# io.net
KiCad netlist of a schematic drawn in Altium Designer
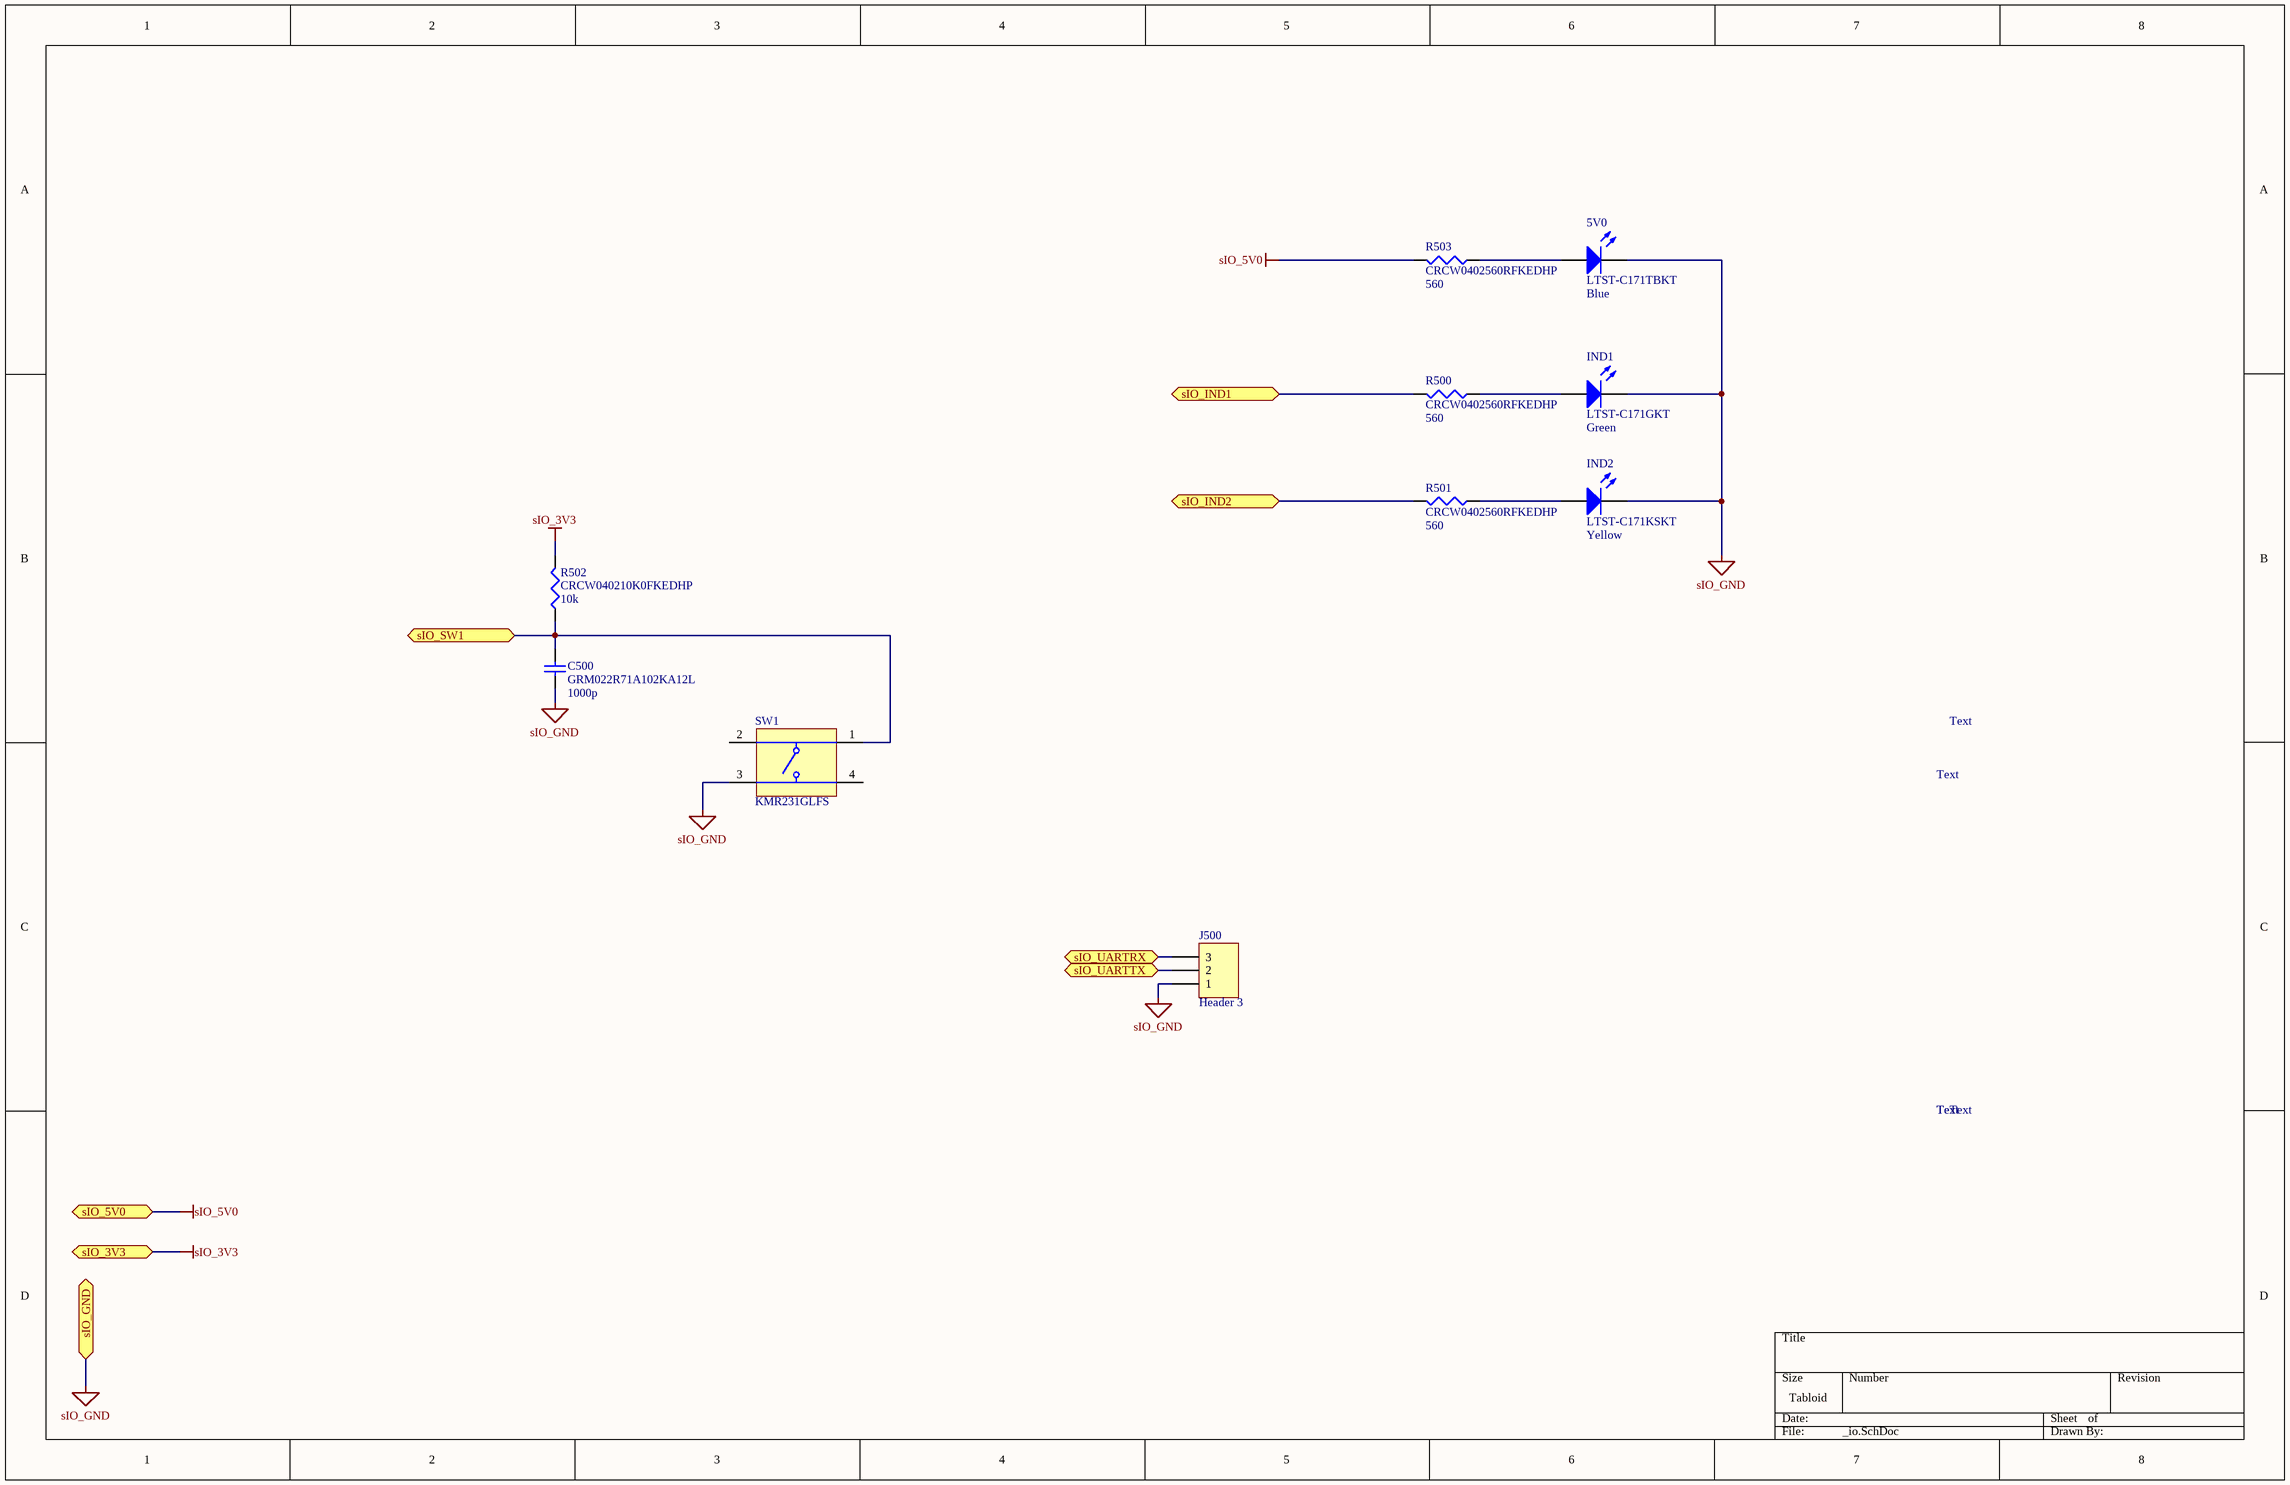
[diagram p0: _io.SchDoc]

(export (version "E")
  (design (tool "Eeschema 10.0.6"))
  (components
    (comp (ref "5V0")
      (value "LTST-C171TBKT")
      (footprint "0805")
      (description "LED")
      (fields (field (name "COLOR") "Blue"))
      (libsource (lib "lite-on") (part "LTST-C171GKT"))
    )
    (comp (ref "C500")
      (value "GRM022R71A102KA12L")
      (footprint "0402")
      (description "-55-125C, 1005, 10V, X7R, ±10%")
      (fields (field (name "ALTIUM_VALUE") "1000p"))
      (libsource (lib "standard_capacitors") (part "GRM022R71AxxxKdddd"))
    )
    (comp (ref "IND1")
      (value "LTST-C171GKT")
      (footprint "0805")
      (description "LED")
      (fields (field (name "COLOR") "Green"))
      (libsource (lib "lite-on") (part "LTST-C171GKT"))
    )
    (comp (ref "IND2")
      (value "LTST-C171KSKT")
      (footprint "0805")
      (description "LED")
      (fields (field (name "COLOR") "Yellow"))
      (libsource (lib "lite-on") (part "LTST-C171KSKT"))
    )
    (comp (ref "J500")
      (value "Header 3")
      (footprint "HDR1X3")
      (description "Header, 3-Pin")
      (fields (field (name "PUBLISHER") "Altium Limited"))
      (libsource (lib "Miscellaneous Connectors") (part "Header 3"))
    )
    (comp (ref "R500")
      (value "CRCW0402560RFKEDHP")
      (footprint "0402")
      (description "0.125W, -55-155C, 1005, 50V, ±1%")
      (fields (field (name "ALTIUM_VALUE") "560"))
      (libsource (lib "standard_resistors") (part "CRCW0402xxxxFKED"))
    )
    (comp (ref "R501")
      (value "CRCW0402560RFKEDHP")
      (footprint "0402")
      (description "0.125W, -55-155C, 1005, 50V, ±1%")
      (fields (field (name "ALTIUM_VALUE") "560"))
      (libsource (lib "standard_resistors") (part "CRCW0402xxxxFKED"))
    )
    (comp (ref "R502")
      (value "CRCW040210K0FKEDHP")
      (footprint "0402")
      (description "0.125W, -55-155C, 1005, 50V, ±1%")
      (fields (field (name "ALTIUM_VALUE") "10k"))
      (libsource (lib "standard_resistors") (part "CRCW0402xxxxFKED"))
    )
    (comp (ref "R503")
      (value "CRCW0402560RFKEDHP")
      (footprint "0402")
      (description "0.125W, -55-155C, 1005, 50V, ±1%")
      (fields (field (name "ALTIUM_VALUE") "560"))
      (libsource (lib "standard_resistors") (part "CRCW0402xxxxFKED"))
    )
    (comp (ref "SW1")
      (value "KMR231GLFS")
      (footprint "CKCP-KMR231GLFS")
      (description "Switch Tactile, SPST, 50 mA, 32 V, -40 to 85 degC, 4-Pin SMD, RoHS, Tape and Reel")
      (fields (field (name "MANUFACTURER") "C&K Components"))
      (libsource (lib "Altium Content Vault") (part "CMP-2000-06516-1"))
    )
  )
  (nets
    (net (code "1") (name "/sIO_IND1") (class "Default")
      (node (ref "R500") (pin "2") (pinfunction "2_2") (pintype "passive"))
    )
    (net (code "2") (name "/sIO_IND2") (class "Default")
      (node (ref "R501") (pin "2") (pinfunction "2_2") (pintype "passive"))
    )
    (net (code "3") (name "/sIO_SW1") (class "Default")
      (node (ref "C500") (pin "2") (pinfunction "2_2") (pintype "passive"))
      (node (ref "R502") (pin "1") (pinfunction "1_1") (pintype "passive"))
      (node (ref "SW1") (pin "1") (pinfunction "1_1") (pintype "passive"))
    )
    (net (code "4") (name "/sIO_UARTRX") (class "Default")
      (node (ref "J500") (pin "3") (pinfunction "3_3") (pintype "passive"))
    )
    (net (code "5") (name "/sIO_UARTTX") (class "Default")
      (node (ref "J500") (pin "2") (pinfunction "2_2") (pintype "passive"))
    )
    (net (code "6") (name "Net-(5V0-A)") (class "Default")
      (node (ref "5V0") (pin "1") (pinfunction "A_1") (pintype "passive"))
      (node (ref "R503") (pin "1") (pinfunction "1_1") (pintype "passive"))
    )
    (net (code "7") (name "Net-(IND1-A)") (class "Default")
      (node (ref "IND1") (pin "1") (pinfunction "A_1") (pintype "passive"))
      (node (ref "R500") (pin "1") (pinfunction "1_1") (pintype "passive"))
    )
    (net (code "8") (name "Net-(IND2-A)") (class "Default")
      (node (ref "IND2") (pin "1") (pinfunction "A_1") (pintype "passive"))
      (node (ref "R501") (pin "1") (pinfunction "1_1") (pintype "passive"))
    )
    (net (code "9") (name "sIO_3V3") (class "Default")
      (node (ref "R502") (pin "2") (pinfunction "2_2") (pintype "passive"))
    )
    (net (code "10") (name "sIO_5V0") (class "Default")
      (node (ref "R503") (pin "2") (pinfunction "2_2") (pintype "passive"))
    )
    (net (code "11") (name "sIO_GND") (class "Default")
      (node (ref "5V0") (pin "2") (pinfunction "K_2") (pintype "passive"))
      (node (ref "C500") (pin "1") (pinfunction "1_1") (pintype "passive"))
      (node (ref "IND1") (pin "2") (pinfunction "K_2") (pintype "passive"))
      (node (ref "IND2") (pin "2") (pinfunction "K_2") (pintype "passive"))
      (node (ref "J500") (pin "1") (pinfunction "1_1") (pintype "passive"))
      (node (ref "SW1") (pin "3") (pinfunction "3_3") (pintype "passive"))
    )
    (net (code "12") (name "unconnected-(SW1-Pad2)") (class "Default")
      (node (ref "SW1") (pin "2") (pinfunction "2_2") (pintype "passive"))
    )
    (net (code "13") (name "unconnected-(SW1-Pad4)") (class "Default")
      (node (ref "SW1") (pin "4") (pinfunction "4_4") (pintype "passive"))
    )
  )
)
